# 12_PERIPHERALS.net
KiCad netlist of a schematic drawn in Altium Designer
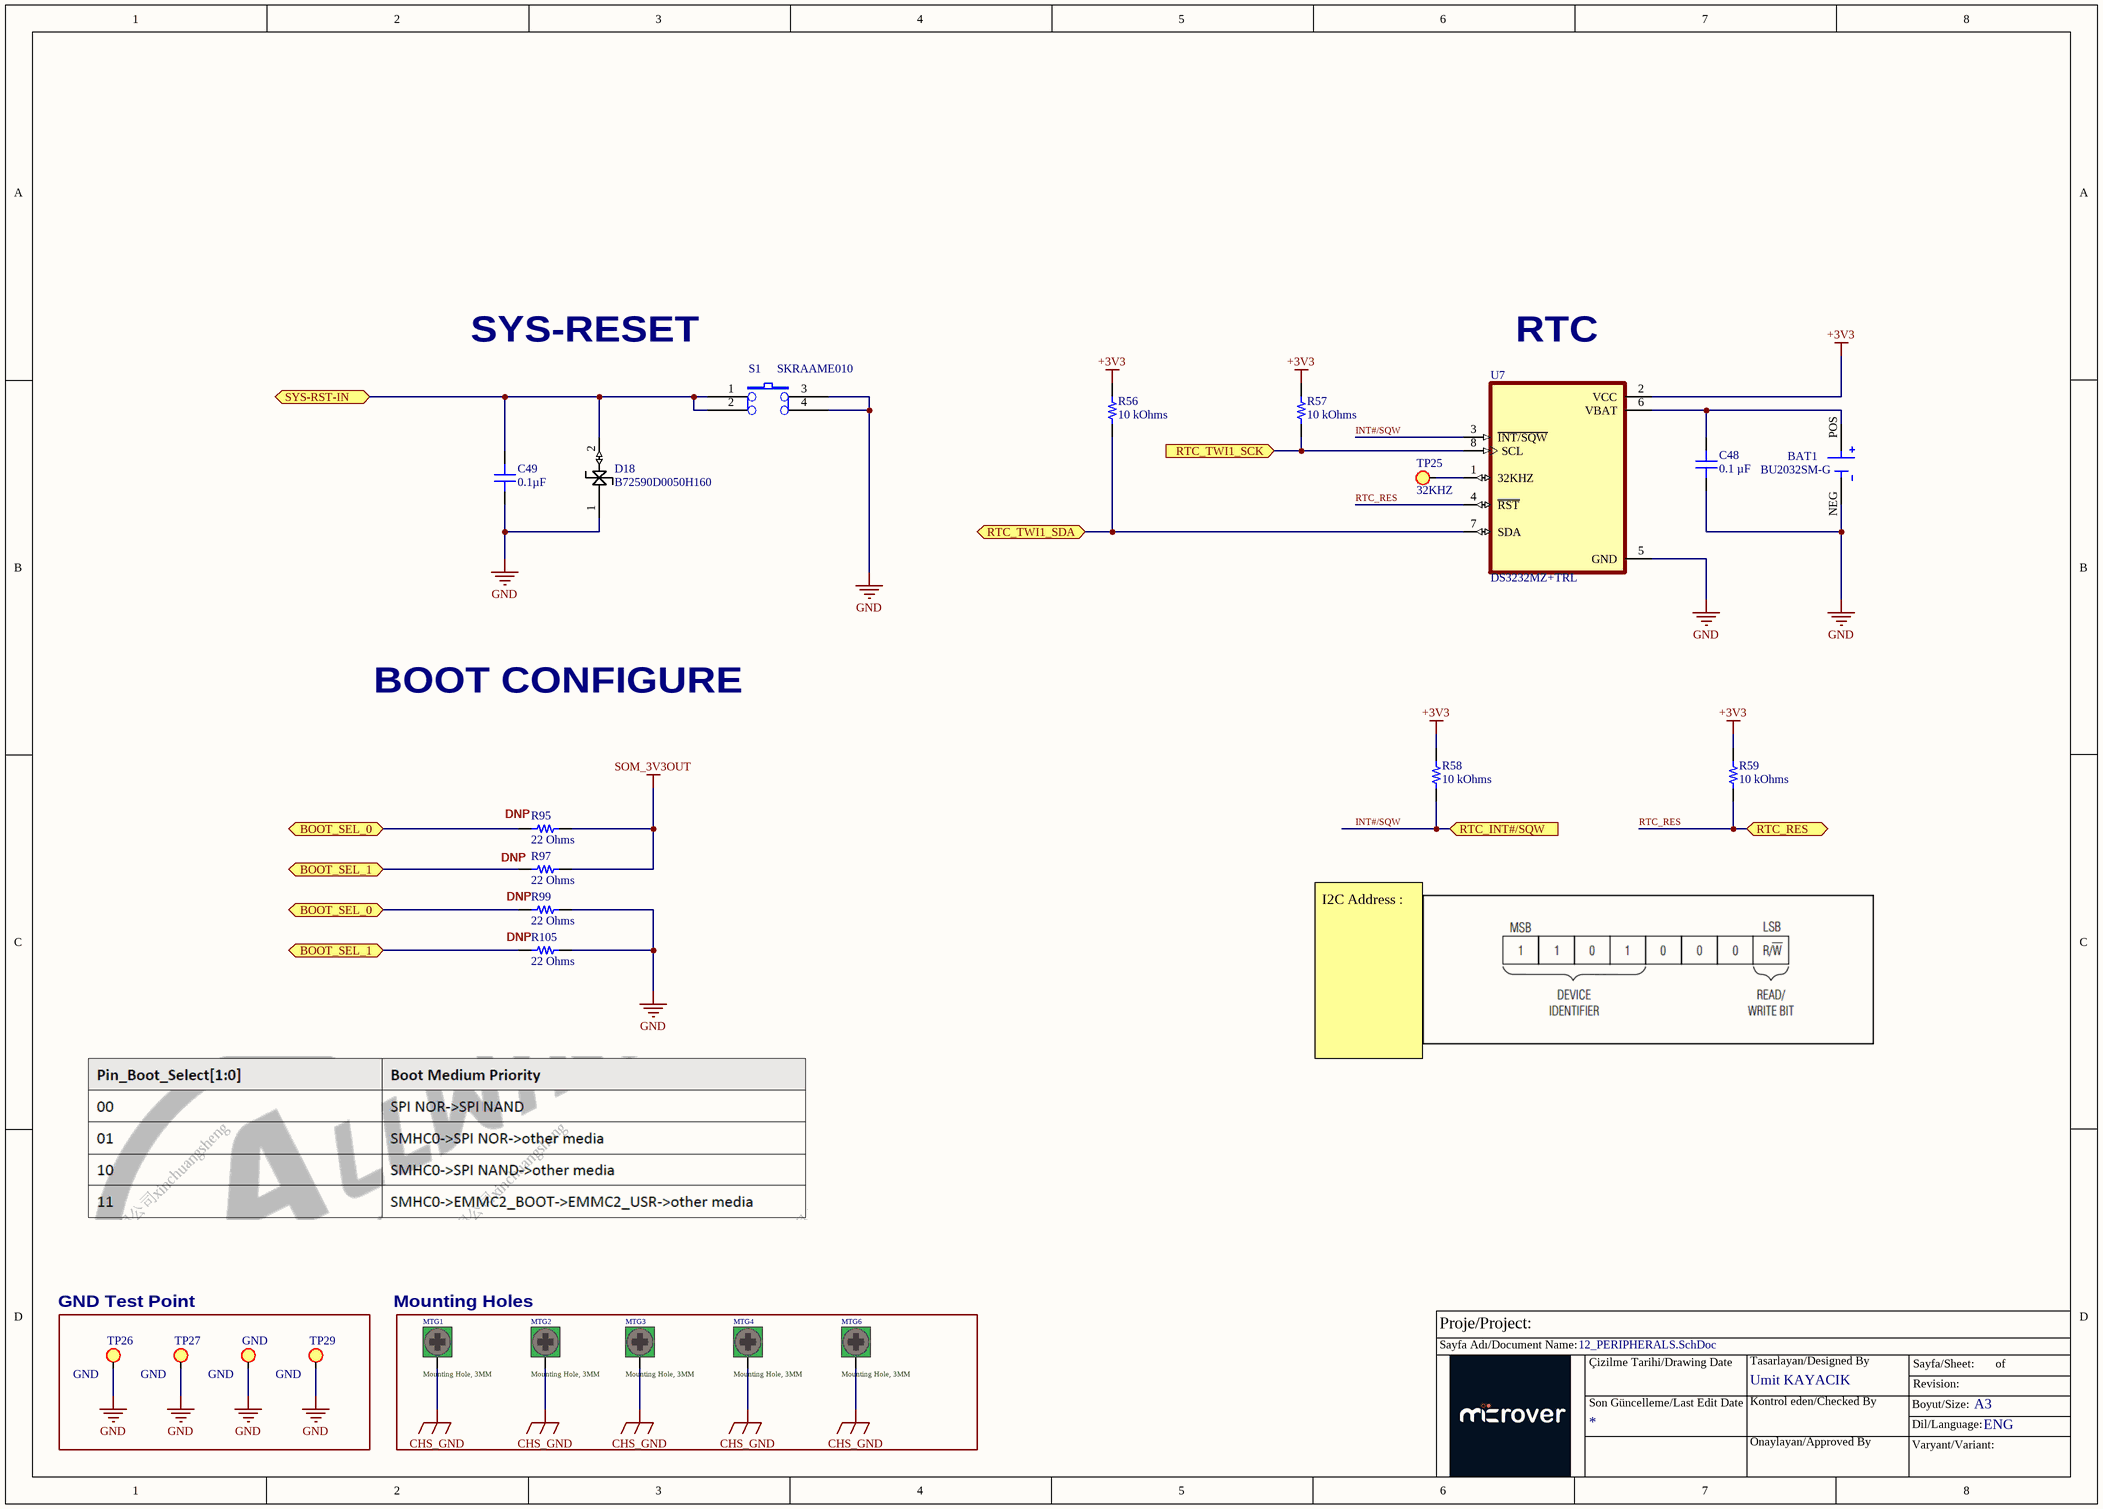
[diagram p0: 12_PERIPHERALS.SchDoc]

(export (version "E")
  (design (tool "Eeschema 10.0.6"))
  (components
    (comp (ref "BAT1")
      (value "BU2032SM-G")
      (footprint "BAT_BU2032SM-G")
      (description "Battery Holder Coin 20MM SMD")
      (fields (field (name "MANUFACTURER") "Memory Protection Devices"))
      (libsource (lib "HW_HOLLAND_NCDM_MONITOR_R1") (part "BU2032SM-G"))
    )
    (comp (ref "C48")
      (value "0.1 µF")
      (footprint "CAP 0402_1005")
      (description "CAP CER 0.1UF 6.3V X5R 0402")
      (fields (field (name "PART NUMBER") "885012105001") (field (name "MANUFACTURER") "Würth Elektronik"))
      (libsource (lib "Celestial Altium Library - altium_library") (part "Capacitor"))
    )
    (comp (ref "C49")
      (value "0.1µF")
      (footprint "CAP 0603_1608")
      (description "CAP CER 0.1UF 50V X7R 0603")
      (fields
        (field (name "PART NUMBER") "ESD35C104K4T2A-24")
        (field (name "MANUFACTURER") "AVX Corporation")
      )
      (libsource (lib "Celestial Altium Library - altium_library") (part "Capacitor"))
    )
    (comp (ref "D18")
      (value "B72590D0050H160")
      (footprint "SOD1005X60N")
      (description "VARISTOR 150V 0402")
      (fields (field (name "MANUFACTURER") "TDK EPCOS"))
      (libsource (lib "HW_HOLLAND_NCDM_MONITOR_R1") (part "B72590D0050H160"))
    )
    (comp (ref "GND")
      (value "GND")
      (footprint "TEST_POINT")
      (libsource (lib "HW_HOLLAND_NCDM_MONITOR_R1") (part "TP_1"))
    )
    (comp (ref "MTG1")
      (value "Mounting Hole, 3MM")
      (footprint "MTG-PTH-3MM")
      (libsource (lib "HW_HOLLAND_NCDM_MONITOR_R1") (part "MTG3MM"))
    )
    (comp (ref "MTG2")
      (value "Mounting Hole, 3MM")
      (footprint "MTG-PTH-3MM")
      (libsource (lib "HW_HOLLAND_NCDM_MONITOR_R1") (part "MTG3MM"))
    )
    (comp (ref "MTG3")
      (value "Mounting Hole, 3MM")
      (footprint "MTG-PTH-3MM")
      (libsource (lib "HW_HOLLAND_NCDM_MONITOR_R1") (part "MTG3MM"))
    )
    (comp (ref "MTG4")
      (value "Mounting Hole, 3MM")
      (footprint "MTG-PTH-3MM")
      (libsource (lib "HW_HOLLAND_NCDM_MONITOR_R1") (part "MTG3MM"))
    )
    (comp (ref "MTG6")
      (value "Mounting Hole, 3MM")
      (footprint "MTG-PTH-3MM")
      (libsource (lib "HW_HOLLAND_NCDM_MONITOR_R1") (part "MTG3MM"))
    )
    (comp (ref "R56")
      (value "10 kOhms")
      (footprint "RES 0402_1005")
      (description "RES 10K OHM 0.1% 1/10W 0402")
      (fields
        (field (name "PART NUMBER") "RP73PF1E10KBTD")
        (field (name "MANUFACTURER") "TE Connectivity Passive Product")
      )
      (libsource (lib "Celestial Altium Library - altium_library") (part "Resistor"))
    )
    (comp (ref "R57")
      (value "10 kOhms")
      (footprint "RES 0402_1005")
      (description "RES 10K OHM 0.1% 1/10W 0402")
      (fields
        (field (name "PART NUMBER") "RP73PF1E10KBTD")
        (field (name "MANUFACTURER") "TE Connectivity Passive Product")
      )
      (libsource (lib "Celestial Altium Library - altium_library") (part "Resistor"))
    )
    (comp (ref "R58")
      (value "10 kOhms")
      (footprint "RES 0402_1005")
      (description "RES 10K OHM 0.1% 1/10W 0402")
      (fields
        (field (name "PART NUMBER") "RP73PF1E10KBTD")
        (field (name "MANUFACTURER") "TE Connectivity Passive Product")
      )
      (libsource (lib "Celestial Altium Library - altium_library") (part "Resistor"))
    )
    (comp (ref "R59")
      (value "10 kOhms")
      (footprint "RES 0402_1005")
      (description "RES 10K OHM 0.1% 1/10W 0402")
      (fields
        (field (name "PART NUMBER") "RP73PF1E10KBTD")
        (field (name "MANUFACTURER") "TE Connectivity Passive Product")
      )
      (libsource (lib "Celestial Altium Library - altium_library") (part "Resistor"))
    )
    (comp (ref "R95")
      (value "22 Ohms")
      (footprint "RES 0402_1005")
      (description "RES 22 OHM 1% 1/16W 0402")
      (fields (field (name "PART NUMBER") "RC0402FR-0722RP") (field (name "MANUFACTURER") "Yageo"))
      (libsource (lib "Celestial Altium Library - altium_library") (part "Resistor"))
    )
    (comp (ref "R97")
      (value "22 Ohms")
      (footprint "RES 0402_1005")
      (description "RES 22 OHM 1% 1/16W 0402")
      (fields (field (name "PART NUMBER") "RC0402FR-0722RP") (field (name "MANUFACTURER") "Yageo"))
      (libsource (lib "Celestial Altium Library - altium_library") (part "Resistor"))
    )
    (comp (ref "R99")
      (value "22 Ohms")
      (footprint "RES 0402_1005")
      (description "RES 22 OHM 1% 1/16W 0402")
      (fields (field (name "PART NUMBER") "RC0402FR-0722RP") (field (name "MANUFACTURER") "Yageo"))
      (libsource (lib "Celestial Altium Library - altium_library") (part "Resistor"))
    )
    (comp (ref "R105")
      (value "22 Ohms")
      (footprint "RES 0402_1005")
      (description "RES 22 OHM 1% 1/16W 0402")
      (fields (field (name "PART NUMBER") "RC0402FR-0722RP") (field (name "MANUFACTURER") "Yageo"))
      (libsource (lib "Celestial Altium Library - altium_library") (part "Resistor"))
    )
    (comp (ref "S1")
      (value "SKRAAME010")
      (footprint "SKRAAME010 - duplicate")
      (description "Key,6.2mm Square with Middle-travel,0.5mm,50mA,12V DC,–40~＋90℃,1.96N,SMT,ALPS")
      (fields (field (name "MANUFACTURER") "ALPS"))
      (libsource (lib "HW_HOLLAND_NCDM_MONITOR_R1") (part "SKRAAME010"))
    )
    (comp (ref "TP25")
      (value "32KHZ")
      (footprint "TEST_POINT")
      (libsource (lib "HW_HOLLAND_NCDM_MONITOR_R1") (part "TP_1"))
    )
    (comp (ref "TP26")
      (value "GND")
      (footprint "TEST_POINT")
      (libsource (lib "HW_HOLLAND_NCDM_MONITOR_R1") (part "TP_1"))
    )
    (comp (ref "TP27")
      (value "GND")
      (footprint "TEST_POINT")
      (libsource (lib "HW_HOLLAND_NCDM_MONITOR_R1") (part "TP_1"))
    )
    (comp (ref "TP29")
      (value "GND")
      (footprint "TEST_POINT")
      (libsource (lib "HW_HOLLAND_NCDM_MONITOR_R1") (part "TP_1"))
    )
    (comp (ref "U7")
      (value "DS3232MZ+TRL")
      (footprint "SOIC127P600X175-8N - duplicate1")
      (description "Real Time Clock (RTC) IC Clock/Calendar 236B I²C, 2-Wire Serial 8-SOIC (0.154, 3.90mm Width)")
      (fields (field (name "MANUFACTURER") "Maxim"))
      (libsource (lib "HW_HOLLAND_NCDM_MONITOR_R1") (part "DS3232MZ+TRL"))
    )
  )
  (nets
    (net (code "1") (name "+3V3") (class "Default")
      (node (ref "R56") (pin "2") (pinfunction "2_2") (pintype "passive"))
      (node (ref "R57") (pin "2") (pinfunction "2_2") (pintype "passive"))
      (node (ref "R58") (pin "2") (pinfunction "2_2") (pintype "passive"))
      (node (ref "R59") (pin "2") (pinfunction "2_2") (pintype "passive"))
      (node (ref "U7") (pin "2") (pinfunction "VCC_2") (pintype "power_in"))
    )
    (net (code "2") (name "/BOOT_SEL_0") (class "Default")
      (node (ref "R95") (pin "1") (pinfunction "1_1") (pintype "passive"))
      (node (ref "R99") (pin "1") (pinfunction "1_1") (pintype "passive"))
    )
    (net (code "3") (name "/BOOT_SEL_1") (class "Default")
      (node (ref "R105") (pin "1") (pinfunction "1_1") (pintype "passive"))
      (node (ref "R97") (pin "1") (pinfunction "1_1") (pintype "passive"))
    )
    (net (code "4") (name "/INT#{slash}SQW") (class "Default")
      (node (ref "R58") (pin "1") (pinfunction "1_1") (pintype "passive"))
      (node (ref "U7") (pin "3") (pinfunction "~{INT/SQW}_3") (pintype "input"))
    )
    (net (code "5") (name "/RTC_RES") (class "Default")
      (node (ref "R59") (pin "1") (pinfunction "1_1") (pintype "passive"))
      (node (ref "U7") (pin "4") (pinfunction "~{RST}_4") (pintype "bidirectional"))
    )
    (net (code "6") (name "/RTC_TWI1_SCK") (class "Default")
      (node (ref "R57") (pin "1") (pinfunction "1_1") (pintype "passive"))
      (node (ref "U7") (pin "8") (pinfunction "SCL_8") (pintype "input"))
    )
    (net (code "7") (name "/RTC_TWI1_SDA") (class "Default")
      (node (ref "R56") (pin "1") (pinfunction "1_1") (pintype "passive"))
      (node (ref "U7") (pin "7") (pinfunction "SDA_7") (pintype "bidirectional"))
    )
    (net (code "8") (name "/SYS-RST-IN") (class "Default")
      (node (ref "C49") (pin "2") (pinfunction "2_2") (pintype "passive"))
      (node (ref "D18") (pin "2") (pinfunction "I/OLINE_2") (pintype "bidirectional"))
      (node (ref "S1") (pin "1") (pinfunction "1_1") (pintype "passive"))
      (node (ref "S1") (pin "2") (pinfunction "2_2") (pintype "passive"))
    )
    (net (code "9") (name "CHS_GND") (class "Default")
      (node (ref "MTG1") (pin "0") (pinfunction "0_0") (pintype "passive"))
      (node (ref "MTG2") (pin "0") (pinfunction "0_0") (pintype "passive"))
      (node (ref "MTG3") (pin "0") (pinfunction "0_0") (pintype "passive"))
      (node (ref "MTG4") (pin "0") (pinfunction "0_0") (pintype "passive"))
      (node (ref "MTG6") (pin "0") (pinfunction "0_0") (pintype "passive"))
    )
    (net (code "10") (name "GND") (class "Default")
      (node (ref "BAT1") (pin "NEG") (pinfunction "NEG_NEG") (pintype "passive"))
      (node (ref "C48") (pin "1") (pinfunction "1_1") (pintype "passive"))
      (node (ref "C49") (pin "1") (pinfunction "1_1") (pintype "passive"))
      (node (ref "D18") (pin "1") (pinfunction "GND_1") (pintype "passive"))
      (node (ref "GND") (pin "1") (pinfunction "TP_1") (pintype "passive"))
      (node (ref "R105") (pin "2") (pinfunction "2_2") (pintype "passive"))
      (node (ref "R99") (pin "2") (pinfunction "2_2") (pintype "passive"))
      (node (ref "S1") (pin "3") (pinfunction "3_3") (pintype "passive"))
      (node (ref "S1") (pin "4") (pinfunction "4_4") (pintype "passive"))
      (node (ref "TP26") (pin "1") (pinfunction "TP_1") (pintype "passive"))
      (node (ref "TP27") (pin "1") (pinfunction "TP_1") (pintype "passive"))
      (node (ref "TP29") (pin "1") (pinfunction "TP_1") (pintype "passive"))
      (node (ref "U7") (pin "5") (pinfunction "GND_5") (pintype "passive"))
    )
    (net (code "11") (name "Net-(TP25-TP)") (class "Default")
      (node (ref "TP25") (pin "1") (pinfunction "TP_1") (pintype "passive"))
      (node (ref "U7") (pin "1") (pinfunction "32KHZ_1") (pintype "bidirectional"))
    )
    (net (code "12") (name "Net-(U7-VBAT)") (class "Default")
      (node (ref "BAT1") (pin "POS") (pinfunction "POS_POS") (pintype "passive"))
      (node (ref "C48") (pin "2") (pinfunction "2_2") (pintype "passive"))
      (node (ref "U7") (pin "6") (pinfunction "VBAT_6") (pintype "power_in"))
    )
    (net (code "13") (name "SOM_3V3OUT") (class "Default")
      (node (ref "R95") (pin "2") (pinfunction "2_2") (pintype "passive"))
      (node (ref "R97") (pin "2") (pinfunction "2_2") (pintype "passive"))
    )
  )
)
